# S_r_c.net
KiCad netlist of a schematic drawn in Altium Designer
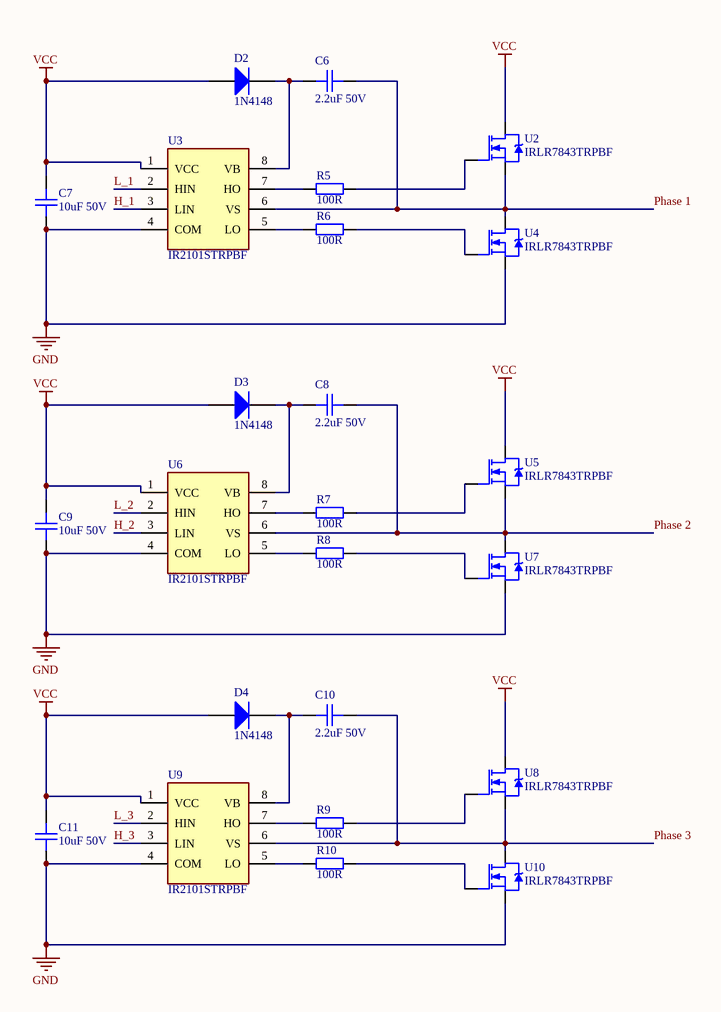
[diagram p0: Sürücü.SchDoc]

(export (version "E")
  (design (tool "Eeschema 10.0.6"))
  (components
    (comp (ref "C6")
      (value "CAP CER 2.2UF 50V X5R 1206")
      (footprint "CAP 1206/3216")
      (description "2.2µF ±10% 50V Ceramic Capacitor X5R 1206 (3216 Metric)")
      (fields (field (name "DEGER") "2.2uF 50V"))
      (libsource (lib "PROJE") (part "2.2uF 50V 1206"))
    )
    (comp (ref "C7")
      (value "CAP CER 10UF 50V X5R 1206")
      (footprint "CAP 1206/3216")
      (description "10µF ±10% 50V Ceramic Capacitor X5R 1206 (3216 Metric)")
      (fields (field (name "DEGER") "10uF 50V"))
      (libsource (lib "PROJE") (part "10uF 50V 1206"))
    )
    (comp (ref "C8")
      (value "CAP CER 2.2UF 50V X5R 1206")
      (footprint "CAP 1206/3216")
      (description "2.2µF ±10% 50V Ceramic Capacitor X5R 1206 (3216 Metric)")
      (fields (field (name "DEGER") "2.2uF 50V"))
      (libsource (lib "PROJE") (part "2.2uF 50V 1206"))
    )
    (comp (ref "C9")
      (value "CAP CER 10UF 50V X5R 1206")
      (footprint "CAP 1206/3216")
      (description "10µF ±10% 50V Ceramic Capacitor X5R 1206 (3216 Metric)")
      (fields (field (name "DEGER") "10uF 50V"))
      (libsource (lib "PROJE") (part "10uF 50V 1206"))
    )
    (comp (ref "C10")
      (value "CAP CER 2.2UF 50V X5R 1206")
      (footprint "CAP 1206/3216")
      (description "2.2µF ±10% 50V Ceramic Capacitor X5R 1206 (3216 Metric)")
      (fields (field (name "DEGER") "2.2uF 50V"))
      (libsource (lib "PROJE") (part "2.2uF 50V 1206"))
    )
    (comp (ref "C11")
      (value "CAP CER 10UF 50V X5R 1206")
      (footprint "CAP 1206/3216")
      (description "10µF ±10% 50V Ceramic Capacitor X5R 1206 (3216 Metric)")
      (fields (field (name "DEGER") "10uF 50V"))
      (libsource (lib "PROJE") (part "10uF 50V 1206"))
    )
    (comp (ref "D2")
      (value "1N4148 Diyot")
      (footprint "SOD-123")
      (description "DIODE GEN PURP 100V 150MA SOD123")
      (fields (field (name "DEGER") "1N4148"))
      (libsource (lib "PROJE") (part "1N4148"))
    )
    (comp (ref "D3")
      (value "1N4148 Diyot")
      (footprint "SOD-123")
      (description "DIODE GEN PURP 100V 150MA SOD123")
      (fields (field (name "DEGER") "1N4148"))
      (libsource (lib "PROJE") (part "1N4148"))
    )
    (comp (ref "D4")
      (value "1N4148 Diyot")
      (footprint "SOD-123")
      (description "DIODE GEN PURP 100V 150MA SOD123")
      (fields (field (name "DEGER") "1N4148"))
      (libsource (lib "PROJE") (part "1N4148"))
    )
    (comp (ref "R5")
      (value "RES SMD 100 OHM 1% 1/8W 0805")
      (footprint "RES_0805")
      (description "100 Ohms ±1% 0.125W, 1/8W Chip Resistor 0805 (2012 Metric) Moisture Resistant Thick Film")
      (fields (field (name "DEGER") "100R"))
      (libsource (lib "PROJE") (part "100R 0805"))
    )
    (comp (ref "R6")
      (value "RES SMD 100 OHM 1% 1/8W 0805")
      (footprint "RES_0805")
      (description "100 Ohms ±1% 0.125W, 1/8W Chip Resistor 0805 (2012 Metric) Moisture Resistant Thick Film")
      (fields (field (name "DEGER") "100R"))
      (libsource (lib "PROJE") (part "100R 0805"))
    )
    (comp (ref "R7")
      (value "RES SMD 100 OHM 1% 1/8W 0805")
      (footprint "RES_0805")
      (description "100 Ohms ±1% 0.125W, 1/8W Chip Resistor 0805 (2012 Metric) Moisture Resistant Thick Film")
      (fields (field (name "DEGER") "100R"))
      (libsource (lib "PROJE") (part "100R 0805"))
    )
    (comp (ref "R8")
      (value "RES SMD 100 OHM 1% 1/8W 0805")
      (footprint "RES_0805")
      (description "100 Ohms ±1% 0.125W, 1/8W Chip Resistor 0805 (2012 Metric) Moisture Resistant Thick Film")
      (fields (field (name "DEGER") "100R"))
      (libsource (lib "PROJE") (part "100R 0805"))
    )
    (comp (ref "R9")
      (value "RES SMD 100 OHM 1% 1/8W 0805")
      (footprint "RES_0805")
      (description "100 Ohms ±1% 0.125W, 1/8W Chip Resistor 0805 (2012 Metric) Moisture Resistant Thick Film")
      (fields (field (name "DEGER") "100R"))
      (libsource (lib "PROJE") (part "100R 0805"))
    )
    (comp (ref "R10")
      (value "RES SMD 100 OHM 1% 1/8W 0805")
      (footprint "RES_0805")
      (description "100 Ohms ±1% 0.125W, 1/8W Chip Resistor 0805 (2012 Metric) Moisture Resistant Thick Film")
      (fields (field (name "DEGER") "100R"))
      (libsource (lib "PROJE") (part "100R 0805"))
    )
    (comp (ref "U2")
      (value "MOSFET N-CH 30V 161A DPAK")
      (footprint "DPAK")
      (description "N-Channel 30V 161A (Tc) 140W (Tc) Surface Mount D-Pak")
      (fields (field (name "DEGER") "IRLR7843TRPBF"))
      (libsource (lib "PROJE") (part "IRLR7843"))
    )
    (comp (ref "U3")
      (value "IC GATE DRVR HALF-BRIDGE 8SOIC")
      (footprint "SOIC8")
      (description "Half-Bridge Gate Driver IC Non-Inverting 8-SOIC")
      (fields (field (name "DEGER") "IR2101STRPBF"))
      (libsource (lib "PROJE") (part "IR2101"))
    )
    (comp (ref "U4")
      (value "MOSFET N-CH 30V 161A DPAK")
      (footprint "DPAK")
      (description "N-Channel 30V 161A (Tc) 140W (Tc) Surface Mount D-Pak")
      (fields (field (name "DEGER") "IRLR7843TRPBF"))
      (libsource (lib "PROJE") (part "IRLR7843"))
    )
    (comp (ref "U5")
      (value "MOSFET N-CH 30V 161A DPAK")
      (footprint "DPAK")
      (description "N-Channel 30V 161A (Tc) 140W (Tc) Surface Mount D-Pak")
      (fields (field (name "DEGER") "IRLR7843TRPBF"))
      (libsource (lib "PROJE") (part "IRLR7843"))
    )
    (comp (ref "U6")
      (value "IC GATE DRVR HALF-BRIDGE 8SOIC")
      (footprint "SOIC8")
      (description "Half-Bridge Gate Driver IC Non-Inverting 8-SOIC")
      (fields (field (name "DEGER") "IR2101STRPBF"))
      (libsource (lib "PROJE") (part "IR2101"))
    )
    (comp (ref "U7")
      (value "MOSFET N-CH 30V 161A DPAK")
      (footprint "DPAK")
      (description "N-Channel 30V 161A (Tc) 140W (Tc) Surface Mount D-Pak")
      (fields (field (name "DEGER") "IRLR7843TRPBF"))
      (libsource (lib "PROJE") (part "IRLR7843"))
    )
    (comp (ref "U8")
      (value "MOSFET N-CH 30V 161A DPAK")
      (footprint "DPAK")
      (description "N-Channel 30V 161A (Tc) 140W (Tc) Surface Mount D-Pak")
      (fields (field (name "DEGER") "IRLR7843TRPBF"))
      (libsource (lib "PROJE") (part "IRLR7843"))
    )
    (comp (ref "U9")
      (value "IC GATE DRVR HALF-BRIDGE 8SOIC")
      (footprint "SOIC8")
      (description "Half-Bridge Gate Driver IC Non-Inverting 8-SOIC")
      (fields (field (name "DEGER") "IR2101STRPBF"))
      (libsource (lib "PROJE") (part "IR2101"))
    )
    (comp (ref "U10")
      (value "MOSFET N-CH 30V 161A DPAK")
      (footprint "DPAK")
      (description "N-Channel 30V 161A (Tc) 140W (Tc) Surface Mount D-Pak")
      (fields (field (name "DEGER") "IRLR7843TRPBF"))
      (libsource (lib "PROJE") (part "IRLR7843"))
    )
  )
  (nets
    (net (code "1") (name "/H_1") (class "Default")
      (node (ref "U3") (pin "3") (pinfunction "LIN_3") (pintype "passive"))
    )
    (net (code "2") (name "/H_2") (class "Default")
      (node (ref "U6") (pin "3") (pinfunction "LIN_3") (pintype "passive"))
    )
    (net (code "3") (name "/H_3") (class "Default")
      (node (ref "U9") (pin "3") (pinfunction "LIN_3") (pintype "passive"))
    )
    (net (code "4") (name "/L_1") (class "Default")
      (node (ref "U3") (pin "2") (pinfunction "HIN_2") (pintype "passive"))
    )
    (net (code "5") (name "/L_2") (class "Default")
      (node (ref "U6") (pin "2") (pinfunction "HIN_2") (pintype "passive"))
    )
    (net (code "6") (name "/L_3") (class "Default")
      (node (ref "U9") (pin "2") (pinfunction "HIN_2") (pintype "passive"))
    )
    (net (code "7") (name "/Phase 1") (class "Default")
      (node (ref "C6") (pin "2") (pinfunction "2_2") (pintype "passive"))
      (node (ref "U2") (pin "3") (pinfunction "S_3") (pintype "passive"))
      (node (ref "U3") (pin "6") (pinfunction "VS_6") (pintype "passive"))
      (node (ref "U4") (pin "4") (pinfunction "D_4") (pintype "passive"))
    )
    (net (code "8") (name "/Phase 2") (class "Default")
      (node (ref "C8") (pin "2") (pinfunction "2_2") (pintype "passive"))
      (node (ref "U5") (pin "3") (pinfunction "S_3") (pintype "passive"))
      (node (ref "U6") (pin "6") (pinfunction "VS_6") (pintype "passive"))
      (node (ref "U7") (pin "4") (pinfunction "D_4") (pintype "passive"))
    )
    (net (code "9") (name "/Phase 3") (class "Default")
      (node (ref "C10") (pin "2") (pinfunction "2_2") (pintype "passive"))
      (node (ref "U10") (pin "4") (pinfunction "D_4") (pintype "passive"))
      (node (ref "U8") (pin "3") (pinfunction "S_3") (pintype "passive"))
      (node (ref "U9") (pin "6") (pinfunction "VS_6") (pintype "passive"))
    )
    (net (code "10") (name "GND") (class "Default")
      (node (ref "C11") (pin "1") (pinfunction "1_1") (pintype "passive"))
      (node (ref "C7") (pin "1") (pinfunction "1_1") (pintype "passive"))
      (node (ref "C9") (pin "1") (pinfunction "1_1") (pintype "passive"))
      (node (ref "U10") (pin "3") (pinfunction "S_3") (pintype "passive"))
      (node (ref "U3") (pin "4") (pinfunction "COM_4") (pintype "passive"))
      (node (ref "U4") (pin "3") (pinfunction "S_3") (pintype "passive"))
      (node (ref "U6") (pin "4") (pinfunction "COM_4") (pintype "passive"))
      (node (ref "U7") (pin "3") (pinfunction "S_3") (pintype "passive"))
      (node (ref "U9") (pin "4") (pinfunction "COM_4") (pintype "passive"))
    )
    (net (code "11") (name "Net-(D2-K)") (class "Default")
      (node (ref "C6") (pin "1") (pinfunction "1_1") (pintype "passive"))
      (node (ref "D2") (pin "2") (pinfunction "K_2") (pintype "passive"))
      (node (ref "U3") (pin "8") (pinfunction "VB_8") (pintype "passive"))
    )
    (net (code "12") (name "Net-(D3-K)") (class "Default")
      (node (ref "C8") (pin "1") (pinfunction "1_1") (pintype "passive"))
      (node (ref "D3") (pin "2") (pinfunction "K_2") (pintype "passive"))
      (node (ref "U6") (pin "8") (pinfunction "VB_8") (pintype "passive"))
    )
    (net (code "13") (name "Net-(D4-K)") (class "Default")
      (node (ref "C10") (pin "1") (pinfunction "1_1") (pintype "passive"))
      (node (ref "D4") (pin "2") (pinfunction "K_2") (pintype "passive"))
      (node (ref "U9") (pin "8") (pinfunction "VB_8") (pintype "passive"))
    )
    (net (code "14") (name "Net-(U2-G)") (class "Default")
      (node (ref "R5") (pin "2") (pinfunction "2_2") (pintype "passive"))
      (node (ref "U2") (pin "1") (pinfunction "G_1") (pintype "passive"))
    )
    (net (code "15") (name "Net-(U3-HO)") (class "Default")
      (node (ref "R5") (pin "1") (pinfunction "1_1") (pintype "passive"))
      (node (ref "U3") (pin "7") (pinfunction "HO_7") (pintype "passive"))
    )
    (net (code "16") (name "Net-(U3-LO)") (class "Default")
      (node (ref "R6") (pin "1") (pinfunction "1_1") (pintype "passive"))
      (node (ref "U3") (pin "5") (pinfunction "LO_5") (pintype "passive"))
    )
    (net (code "17") (name "Net-(U4-G)") (class "Default")
      (node (ref "R6") (pin "2") (pinfunction "2_2") (pintype "passive"))
      (node (ref "U4") (pin "1") (pinfunction "G_1") (pintype "passive"))
    )
    (net (code "18") (name "Net-(U5-G)") (class "Default")
      (node (ref "R7") (pin "2") (pinfunction "2_2") (pintype "passive"))
      (node (ref "U5") (pin "1") (pinfunction "G_1") (pintype "passive"))
    )
    (net (code "19") (name "Net-(U6-HO)") (class "Default")
      (node (ref "R7") (pin "1") (pinfunction "1_1") (pintype "passive"))
      (node (ref "U6") (pin "7") (pinfunction "HO_7") (pintype "passive"))
    )
    (net (code "20") (name "Net-(U6-LO)") (class "Default")
      (node (ref "R8") (pin "1") (pinfunction "1_1") (pintype "passive"))
      (node (ref "U6") (pin "5") (pinfunction "LO_5") (pintype "passive"))
    )
    (net (code "21") (name "Net-(U7-G)") (class "Default")
      (node (ref "R8") (pin "2") (pinfunction "2_2") (pintype "passive"))
      (node (ref "U7") (pin "1") (pinfunction "G_1") (pintype "passive"))
    )
    (net (code "22") (name "Net-(U8-G)") (class "Default")
      (node (ref "R9") (pin "2") (pinfunction "2_2") (pintype "passive"))
      (node (ref "U8") (pin "1") (pinfunction "G_1") (pintype "passive"))
    )
    (net (code "23") (name "Net-(U9-HO)") (class "Default")
      (node (ref "R9") (pin "1") (pinfunction "1_1") (pintype "passive"))
      (node (ref "U9") (pin "7") (pinfunction "HO_7") (pintype "passive"))
    )
    (net (code "24") (name "Net-(U9-LO)") (class "Default")
      (node (ref "R10") (pin "1") (pinfunction "1_1") (pintype "passive"))
      (node (ref "U9") (pin "5") (pinfunction "LO_5") (pintype "passive"))
    )
    (net (code "25") (name "Net-(U10-G)") (class "Default")
      (node (ref "R10") (pin "2") (pinfunction "2_2") (pintype "passive"))
      (node (ref "U10") (pin "1") (pinfunction "G_1") (pintype "passive"))
    )
    (net (code "26") (name "VCC") (class "Default")
      (node (ref "C11") (pin "2") (pinfunction "2_2") (pintype "passive"))
      (node (ref "C7") (pin "2") (pinfunction "2_2") (pintype "passive"))
      (node (ref "C9") (pin "2") (pinfunction "2_2") (pintype "passive"))
      (node (ref "D2") (pin "1") (pinfunction "A_1") (pintype "passive"))
      (node (ref "D3") (pin "1") (pinfunction "A_1") (pintype "passive"))
      (node (ref "D4") (pin "1") (pinfunction "A_1") (pintype "passive"))
      (node (ref "U2") (pin "4") (pinfunction "D_4") (pintype "passive"))
      (node (ref "U3") (pin "1") (pinfunction "VCC_1") (pintype "passive"))
      (node (ref "U5") (pin "4") (pinfunction "D_4") (pintype "passive"))
      (node (ref "U6") (pin "1") (pinfunction "VCC_1") (pintype "passive"))
      (node (ref "U8") (pin "4") (pinfunction "D_4") (pintype "passive"))
      (node (ref "U9") (pin "1") (pinfunction "VCC_1") (pintype "passive"))
    )
  )
)
